# SV601286G_Schematic.net
KiCad netlist of a schematic drawn in Altium Designer
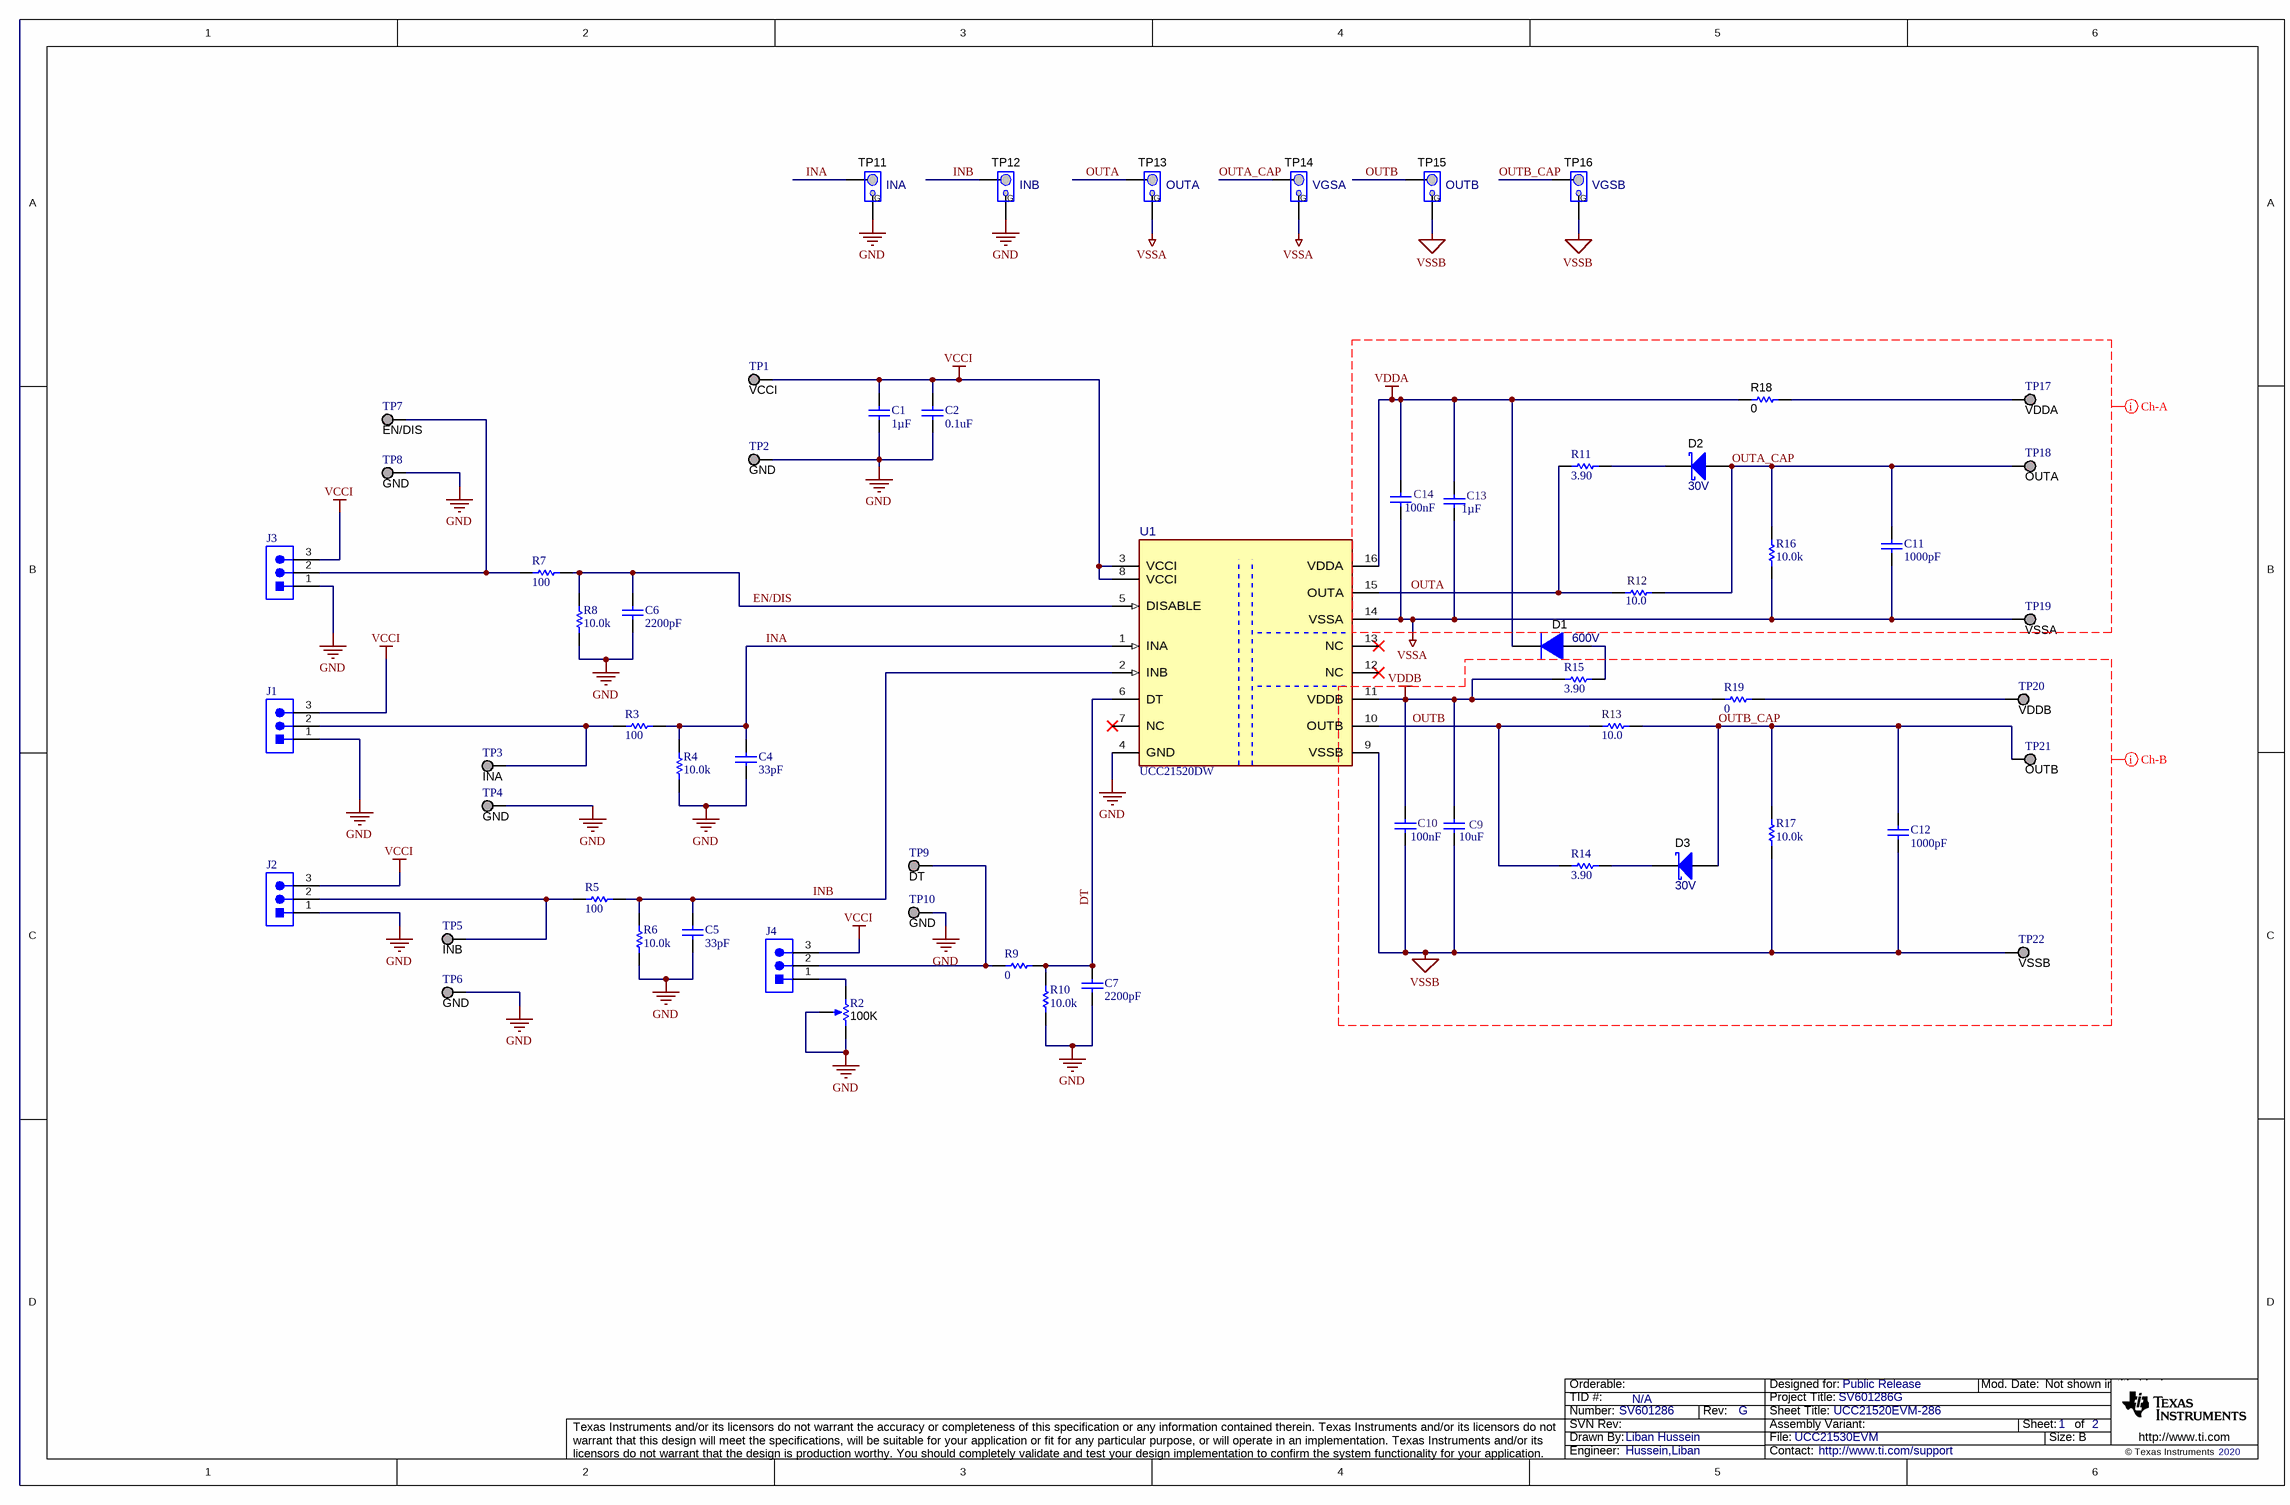
[diagram p0: SV601286G_Schematic.SchDoc]

(export (version "E")
  (design (tool "Eeschema 10.0.6"))
  (components
    (comp (ref "C1")
      (value "CL21B105KBFNFNE")
      (footprint "0805_HV1")
      (description "CAP, CERM, 1 µF, 50 V,+/- 10%, X7R, 0805")
      (fields (field (name "MANUFACTURER") "Samsung") (field (name "VALUEDISPLAYED") "1µF"))
      (libsource (lib "Altium Vault - TI") (part "Capacitor"))
    )
    (comp (ref "C2")
      (value "C1608X7R1E104K080AA")
      (footprint "0603L")
      (description "CAP, CERM, 0.1 uF, 25 V, +/- 10%, X7R, 0603")
      (fields
        (field (name "MANUFACTURER") "TDK")
        (field (name "VALUEDISPLAYED") "0.1uF")
        (field (name "PUBLISHER") "Texas Instruments")
      )
      (libsource (lib "Altium Vault - TI") (part "Capacitor"))
    )
    (comp (ref "C4")
      (value "GRM1885C1H330JA01D")
      (footprint "0603L")
      (description "CAP, CERM, 33 pF, 50 V, +/- 5%, C0G/NP0, 0603")
      (fields
        (field (name "MANUFACTURER") "MuRata")
        (field (name "VALUEDISPLAYED") "33pF")
        (field (name "PUBLISHER") "Texas Instruments")
      )
      (libsource (lib "Altium Vault - TI") (part "Capacitor"))
    )
    (comp (ref "C5")
      (value "GRM1885C1H330JA01D")
      (footprint "0603L")
      (description "CAP, CERM, 33 pF, 50 V, +/- 5%, C0G/NP0, 0603")
      (fields
        (field (name "MANUFACTURER") "MuRata")
        (field (name "VALUEDISPLAYED") "33pF")
        (field (name "PUBLISHER") "Texas Instruments")
      )
      (libsource (lib "Altium Vault - TI") (part "Capacitor"))
    )
    (comp (ref "C6")
      (value "C0603C222K5RACTU")
      (footprint "0603L")
      (description "CAP, CERM, 2200 pF, 50 V, +/- 10%, X7R, 0603")
      (fields
        (field (name "MANUFACTURER") "Kemet")
        (field (name "VALUEDISPLAYED") "2200pF")
        (field (name "PUBLISHER") "Texas Instruments")
      )
      (libsource (lib "Altium Vault - TI") (part "Capacitor"))
    )
    (comp (ref "C7")
      (value "C0603C222K5RACTU")
      (footprint "0603L")
      (description "CAP, CERM, 2200 pF, 50 V, +/- 10%, X7R, 0603")
      (fields
        (field (name "MANUFACTURER") "Kemet")
        (field (name "VALUEDISPLAYED") "2200pF")
        (field (name "PUBLISHER") "Texas Instruments")
      )
      (libsource (lib "Altium Vault - TI") (part "Capacitor"))
    )
    (comp (ref "C9")
      (value "CL31B106KBHNNNE")
      (footprint "1206_180")
      (description "CAP, CERM, 10 uF, 50 V, +/- 10%, X7R, 1206")
      (fields
        (field (name "MANUFACTURER") "Samsung")
        (field (name "VALUEDISPLAYED") "10uF")
        (field (name "PUBLISHER") "Texas Instruments")
      )
      (libsource (lib "Altium Vault - TI") (part "Capacitor"))
    )
    (comp (ref "C10")
      (value "C0805C104J5RACTU")
      (footprint "0805_HV")
      (description "CAP, CERM, 0.1 uF, 50 V, +/- 5%, X7R, 0805")
      (fields
        (field (name "MANUFACTURER") "Kemet")
        (field (name "CAP_F") "100nF")
        (field (name "PUBLISHER") "Texas Instruments")
      )
      (libsource (lib "Altium Vault - TI") (part "Capacitor"))
    )
    (comp (ref "C11")
      (value "GRM3195C1H102JA01D")
      (footprint "1206L")
      (description "CAP, CERM, 1000 pF, 50 V, +/- 5%, C0G/NP0, 1206")
      (fields
        (field (name "MANUFACTURER") "MuRata")
        (field (name "VALUEDISPLAYED") "1000pF")
        (field (name "PUBLISHER") "Texas Instruments")
      )
      (libsource (lib "Altium Vault - TI") (part "Capacitor"))
    )
    (comp (ref "C12")
      (value "GRM3195C1H102JA01D")
      (footprint "1206L")
      (description "CAP, CERM, 1000 pF, 50 V, +/- 5%, C0G/NP0, 1206")
      (fields
        (field (name "MANUFACTURER") "MuRata")
        (field (name "VALUEDISPLAYED") "1000pF")
        (field (name "PUBLISHER") "Texas Instruments")
      )
      (libsource (lib "Altium Vault - TI") (part "Capacitor"))
    )
    (comp (ref "C13")
      (value "CL21B105KBFNFNE")
      (footprint "0805_HV")
      (description "CAP, CERM, 1 µF, 50 V,+/- 10%, X7R, 0805")
      (fields (field (name "MANUFACTURER") "Samsung") (field (name "VALUEDISPLAYED") "1µF"))
      (libsource (lib "Altium Vault - TI") (part "CMP-0080611-1"))
    )
    (comp (ref "C14")
      (value "C0805C104J5RACTU")
      (footprint "0805_HV")
      (description "CAP, CERM, 0.1 uF, 50 V, +/- 5%, X7R, 0805")
      (fields
        (field (name "MANUFACTURER") "Kemet")
        (field (name "CAP_F") "100nF")
        (field (name "PUBLISHER") "Texas Instruments")
      )
      (libsource (lib "Altium Vault - TI") (part "Capacitor"))
    )
    (comp (ref "D1")
      (value "600V")
      (footprint "SMA")
      (description "Diode, Ultrafast, 600 V, 1 A, SMA")
      (fields (field (name "PARTNUMBER") "STTH1R06A") (field (name "MANUFACTURER") "STMicroelectronics"))
      (libsource (lib "Altium Vault - TI") (part "DIODE"))
    )
    (comp (ref "D2")
      (value "30V")
      (footprint "MicroSMP")
      (description "Diode, Schottky, 30 V, 1 A, AEC-Q101, MicroSMP")
      (fields
        (field (name "MANUFACTURER") "Vishay-Semiconductor")
        (field (name "PARTNUMBER") "MSS1P3L-M3/89A")
      )
      (libsource (lib "Altium Vault - TI") (part "DIODE_SCHOTTKY"))
    )
    (comp (ref "D3")
      (value "30V")
      (footprint "MicroSMP")
      (description "Diode, Schottky, 30 V, 1 A, AEC-Q101, MicroSMP")
      (fields
        (field (name "MANUFACTURER") "Vishay-Semiconductor")
        (field (name "PARTNUMBER") "MSS1P3L-M3/89A")
      )
      (libsource (lib "Altium Vault - TI") (part "DIODE_SCHOTTKY"))
    )
    (comp (ref "J1")
      (value "TSW-103-07-T-S")
      (footprint "Samtec_TSW-103-07-T-S")
      (description "Header, 2.54 mm, 3x1, Tin, TH")
      (fields (field (name "MANUFACTURER") "Samtec"))
      (libsource (lib "Altium Vault - TI") (part "Header_3x1"))
    )
    (comp (ref "J2")
      (value "TSW-103-07-T-S")
      (footprint "Samtec_TSW-103-07-T-S")
      (description "Header, 2.54 mm, 3x1, Tin, TH")
      (fields (field (name "MANUFACTURER") "Samtec"))
      (libsource (lib "Altium Vault - TI") (part "Header_3x1"))
    )
    (comp (ref "J3")
      (value "TSW-103-07-T-S")
      (footprint "Samtec_TSW-103-07-T-S")
      (description "Header, 2.54 mm, 3x1, Tin, TH")
      (fields (field (name "MANUFACTURER") "Samtec"))
      (libsource (lib "Altium Vault - TI") (part "Header_3x1"))
    )
    (comp (ref "J4")
      (value "TSW-103-07-T-S")
      (footprint "Samtec_TSW-103-07-T-S")
      (description "Header, 2.54 mm, 3x1, Tin, TH")
      (fields (field (name "MANUFACTURER") "Samtec"))
      (libsource (lib "Altium Vault - TI") (part "Header_3x1"))
    )
    (comp (ref "R2")
      (value "100K")
      (footprint "TRIM_3224X")
      (description "Trimmer, 100 K, 0.25 W, SMD")
      (fields
        (field (name "PARTNUMBER") "3224X-1-104E")
        (field (name "MANUFACTURER") "Bourns")
        (field (name "PUBLISHER") "Texas Instruments")
      )
      (libsource (lib "Altium Vault - TI") (part "Potentiometer"))
    )
    (comp (ref "R3")
      (value "CRCW0603100RFKEA")
      (footprint "0603L")
      (description "RES, 100, 1%, 0.1 W, AEC-Q200 Grade 0, 0603")
      (fields (field (name "MANUFACTURER") "Vishay-Dale") (field (name "VALUEDISPLAYED") "100"))
      (libsource (lib "Altium Vault - TI") (part "Resistor"))
    )
    (comp (ref "R4")
      (value "ERJ-3EKF1002V")
      (footprint "0603L")
      (description "RES, 10.0 k, 1%, 0.1 W, 0603")
      (fields
        (field (name "MANUFACTURER") "Panasonic")
        (field (name "VALUEDISPLAYED") "10.0k")
        (field (name "PUBLISHER") "Texas Instruments")
      )
      (libsource (lib "Altium Vault - TI") (part "CMP-0022684-3"))
    )
    (comp (ref "R5")
      (value "CRCW0603100RFKEA")
      (footprint "0603L")
      (description "RES, 100, 1%, 0.1 W, AEC-Q200 Grade 0, 0603")
      (fields (field (name "MANUFACTURER") "Vishay-Dale") (field (name "VALUEDISPLAYED") "100"))
      (libsource (lib "Altium Vault - TI") (part "Resistor"))
    )
    (comp (ref "R6")
      (value "ERJ-3EKF1002V")
      (footprint "0603L")
      (description "RES, 10.0 k, 1%, 0.1 W, 0603")
      (fields
        (field (name "MANUFACTURER") "Panasonic")
        (field (name "VALUEDISPLAYED") "10.0k")
        (field (name "PUBLISHER") "Texas Instruments")
      )
      (libsource (lib "Altium Vault - TI") (part "CMP-0022684-3"))
    )
    (comp (ref "R7")
      (value "CRCW0603100RFKEA")
      (footprint "0603_HV")
      (description "RES, 100, 1%, 0.1 W, AEC-Q200 Grade 0, 0603")
      (fields (field (name "MANUFACTURER") "Vishay-Dale") (field (name "VALUEDISPLAYED") "100"))
      (libsource (lib "Altium Vault - TI") (part "Resistor"))
    )
    (comp (ref "R8")
      (value "ERJ-3EKF1002V")
      (footprint "0603L")
      (description "RES, 10.0 k, 1%, 0.1 W, 0603")
      (fields
        (field (name "MANUFACTURER") "Panasonic")
        (field (name "VALUEDISPLAYED") "10.0k")
        (field (name "PUBLISHER") "Texas Instruments")
      )
      (libsource (lib "Altium Vault - TI") (part "Resistor"))
    )
    (comp (ref "R9")
      (value "RCS06030000Z0EA")
      (footprint "0603L")
      (description "RES, 0, 0%, 0.25 W, AEC-Q200 Grade 0, 0603")
      (fields (field (name "MANUFACTURER") "Vishay-Dale") (field (name "VALUEDISPLAYED") "0"))
      (libsource (lib "Altium Vault - TI") (part "CMP-0081973-1"))
    )
    (comp (ref "R10")
      (value "ERJ-3EKF1002V")
      (footprint "0603L")
      (description "RES, 10.0 k, 1%, 0.1 W, 0603")
      (fields
        (field (name "MANUFACTURER") "Panasonic")
        (field (name "VALUEDISPLAYED") "10.0k")
        (field (name "PUBLISHER") "Texas Instruments")
      )
      (libsource (lib "Altium Vault - TI") (part "CMP-0022684-3"))
    )
    (comp (ref "R11")
      (value "RC0805FR-073R9L")
      (footprint "0805_HV1")
      (description "RES, 3.90, 1%, 0.125 W, 0805")
      (fields
        (field (name "MANUFACTURER") "Yageo America")
        (field (name "VALUEDISPLAYED") "3.90")
        (field (name "PUBLISHER") "Texas Instruments")
      )
      (libsource (lib "Altium Vault - TI") (part "CMP-0021926-2"))
    )
    (comp (ref "R12")
      (value "ERJ-P06F10R0V")
      (footprint "0805_HV1")
      (description "RES, 10.0, 1%, 0.5 W, AEC-Q200 Grade 0, 0805")
      (fields
        (field (name "MANUFACTURER") "Panasonic")
        (field (name "VALUEDISPLAYED") "10.0")
        (field (name "PUBLISHER") "Texas Instruments")
      )
      (libsource (lib "Altium Vault - TI") (part "Resistor"))
    )
    (comp (ref "R13")
      (value "ERJ-P06F10R0V")
      (footprint "0805_HV1")
      (description "RES, 10.0, 1%, 0.5 W, AEC-Q200 Grade 0, 0805")
      (fields
        (field (name "MANUFACTURER") "Panasonic")
        (field (name "VALUEDISPLAYED") "10.0")
        (field (name "PUBLISHER") "Texas Instruments")
      )
      (libsource (lib "Altium Vault - TI") (part "Resistor"))
    )
    (comp (ref "R14")
      (value "RC0805FR-073R9L")
      (footprint "0805_HV1")
      (description "RES, 3.90, 1%, 0.125 W, 0805")
      (fields
        (field (name "MANUFACTURER") "Yageo America")
        (field (name "VALUEDISPLAYED") "3.90")
        (field (name "PUBLISHER") "Texas Instruments")
      )
      (libsource (lib "Altium Vault - TI") (part "CMP-0021926-2"))
    )
    (comp (ref "R15")
      (value "RC0805FR-073R9L")
      (footprint "0805_HV")
      (description "RES, 3.90, 1%, 0.125 W, 0805")
      (fields
        (field (name "MANUFACTURER") "Yageo America")
        (field (name "VALUEDISPLAYED") "3.90")
        (field (name "PUBLISHER") "Texas Instruments")
      )
      (libsource (lib "Altium Vault - TI") (part "CMP-0021926-2"))
    )
    (comp (ref "R16")
      (value "ERJ-3EKF1002V")
      (footprint "0603L")
      (description "RES, 10.0 k, 1%, 0.1 W, 0603")
      (fields
        (field (name "MANUFACTURER") "Panasonic")
        (field (name "VALUEDISPLAYED") "10.0k")
        (field (name "PUBLISHER") "Texas Instruments")
      )
      (libsource (lib "Altium Vault - TI") (part "CMP-0022684-3"))
    )
    (comp (ref "R17")
      (value "ERJ-3EKF1002V")
      (footprint "0603L")
      (description "RES, 10.0 k, 1%, 0.1 W, 0603")
      (fields
        (field (name "MANUFACTURER") "Panasonic")
        (field (name "VALUEDISPLAYED") "10.0k")
        (field (name "PUBLISHER") "Texas Instruments")
      )
      (libsource (lib "Altium Vault - TI") (part "CMP-0022684-3"))
    )
    (comp (ref "R18")
      (value "RCS06030000Z0EA")
      (footprint "0603L")
      (description "RES, 0, 0%, 0.25 W, AEC-Q200 Grade 0, 0603")
      (fields (field (name "MANUFACTURER") "Vishay-Dale") (field (name "VALUEDISPLAYED") "0"))
      (libsource (lib "Altium Vault - TI") (part "CMP-0081973-1"))
    )
    (comp (ref "R19")
      (value "RCS06030000Z0EA")
      (footprint "0603L")
      (description "RES, 0, 0%, 0.25 W, AEC-Q200 Grade 0, 0603")
      (fields (field (name "MANUFACTURER") "Vishay-Dale") (field (name "VALUEDISPLAYED") "0"))
      (libsource (lib "Altium Vault - TI") (part "CMP-0081973-1"))
    )
    (comp (ref "TP1")
      (value "VCCI")
      (footprint "Keystone_5019")
      (description "Test Point, Miniature, SMT")
      (fields
        (field (name "MANUFACTURER") "Keystone")
        (field (name "PARTNUMBER") "5019")
        (field (name "PUBLISHER") "Texas Instruments")
      )
      (libsource (lib "Altium Vault - TI") (part "Testpoint_Gray"))
    )
    (comp (ref "TP2")
      (value "GND")
      (footprint "Keystone_5019")
      (description "Test Point, Miniature, SMT")
      (fields
        (field (name "MANUFACTURER") "Keystone")
        (field (name "PARTNUMBER") "5019")
        (field (name "PUBLISHER") "Texas Instruments")
      )
      (libsource (lib "Altium Vault - TI") (part "Testpoint_Gray"))
    )
    (comp (ref "TP3")
      (value "INA")
      (footprint "Keystone_5019")
      (description "Test Point, Miniature, SMT")
      (fields
        (field (name "MANUFACTURER") "Keystone")
        (field (name "PARTNUMBER") "5019")
        (field (name "PUBLISHER") "Texas Instruments")
      )
      (libsource (lib "Altium Vault - TI") (part "Testpoint_Gray"))
    )
    (comp (ref "TP4")
      (value "GND")
      (footprint "Keystone_5019")
      (description "Test Point, Miniature, SMT")
      (fields
        (field (name "MANUFACTURER") "Keystone")
        (field (name "PARTNUMBER") "5019")
        (field (name "PUBLISHER") "Texas Instruments")
      )
      (libsource (lib "Altium Vault - TI") (part "Testpoint_Gray"))
    )
    (comp (ref "TP5")
      (value "INB")
      (footprint "Keystone_5019")
      (description "Test Point, Miniature, SMT")
      (fields
        (field (name "MANUFACTURER") "Keystone")
        (field (name "PARTNUMBER") "5019")
        (field (name "PUBLISHER") "Texas Instruments")
      )
      (libsource (lib "Altium Vault - TI") (part "Testpoint_Gray"))
    )
    (comp (ref "TP6")
      (value "GND")
      (footprint "Keystone_5019")
      (description "Test Point, Miniature, SMT")
      (fields
        (field (name "MANUFACTURER") "Keystone")
        (field (name "PARTNUMBER") "5019")
        (field (name "PUBLISHER") "Texas Instruments")
      )
      (libsource (lib "Altium Vault - TI") (part "Testpoint_Gray"))
    )
    (comp (ref "TP7")
      (value "EN/DIS")
      (footprint "Keystone_5019")
      (description "Test Point, Miniature, SMT")
      (fields
        (field (name "MANUFACTURER") "Keystone")
        (field (name "PARTNUMBER") "5019")
        (field (name "PUBLISHER") "Texas Instruments")
      )
      (libsource (lib "Altium Vault - TI") (part "Testpoint_Gray"))
    )
    (comp (ref "TP8")
      (value "GND")
      (footprint "Keystone_5019")
      (description "Test Point, Miniature, SMT")
      (fields
        (field (name "MANUFACTURER") "Keystone")
        (field (name "PARTNUMBER") "5019")
        (field (name "PUBLISHER") "Texas Instruments")
      )
      (libsource (lib "Altium Vault - TI") (part "Testpoint_Gray"))
    )
    (comp (ref "TP9")
      (value "DT")
      (footprint "Keystone_5019")
      (description "Test Point, Miniature, SMT")
      (fields
        (field (name "MANUFACTURER") "Keystone")
        (field (name "PARTNUMBER") "5019")
        (field (name "PUBLISHER") "Texas Instruments")
      )
      (libsource (lib "Altium Vault - TI") (part "Testpoint_Gray"))
    )
    (comp (ref "TP10")
      (value "GND")
      (footprint "Keystone_5019")
      (description "Test Point, Miniature, SMT")
      (fields
        (field (name "MANUFACTURER") "Keystone")
        (field (name "PARTNUMBER") "5019")
        (field (name "PUBLISHER") "Texas Instruments")
      )
      (libsource (lib "Altium Vault - TI") (part "Testpoint_Gray"))
    )
    (comp (ref "TP11")
      (value "INA")
      (footprint "TESTPOINT_PIGTAIL")
      (description "PIGTAIL")
      (fields
        (field (name "MANUFACTURER") "Texas Instruments")
        (field (name "PARTNUMBER") "TESTPOINT_PIGTAIL")
        (field (name "PUBLISHER") "Texas Instruments")
      )
      (libsource (lib "Altium Vault - TI") (part "TESTPOINT_PIGTAIL"))
    )
    (comp (ref "TP12")
      (value "INB")
      (footprint "TESTPOINT_PIGTAIL")
      (description "PIGTAIL")
      (fields
        (field (name "MANUFACTURER") "Texas Instruments")
        (field (name "PARTNUMBER") "TESTPOINT_PIGTAIL")
        (field (name "PUBLISHER") "Texas Instruments")
      )
      (libsource (lib "Altium Vault - TI") (part "TESTPOINT_PIGTAIL"))
    )
    (comp (ref "TP13")
      (value "OUTA")
      (footprint "TESTPOINT_PIGTAIL")
      (description "PIGTAIL")
      (fields
        (field (name "MANUFACTURER") "Texas Instruments")
        (field (name "PARTNUMBER") "TESTPOINT_PIGTAIL")
        (field (name "PUBLISHER") "Texas Instruments")
      )
      (libsource (lib "Altium Vault - TI") (part "TESTPOINT_PIGTAIL"))
    )
    (comp (ref "TP14")
      (value "VGSA")
      (footprint "TESTPOINT_PIGTAIL")
      (description "PIGTAIL")
      (fields
        (field (name "MANUFACTURER") "Texas Instruments")
        (field (name "PARTNUMBER") "TESTPOINT_PIGTAIL")
        (field (name "PUBLISHER") "Texas Instruments")
      )
      (libsource (lib "Altium Vault - TI") (part "TESTPOINT_PIGTAIL"))
    )
    (comp (ref "TP15")
      (value "OUTB")
      (footprint "TESTPOINT_PIGTAIL")
      (description "PIGTAIL")
      (fields
        (field (name "MANUFACTURER") "Texas Instruments")
        (field (name "PARTNUMBER") "TESTPOINT_PIGTAIL")
        (field (name "PUBLISHER") "Texas Instruments")
      )
      (libsource (lib "Altium Vault - TI") (part "TESTPOINT_PIGTAIL"))
    )
    (comp (ref "TP16")
      (value "VGSB")
      (footprint "TESTPOINT_PIGTAIL")
      (description "PIGTAIL")
      (fields
        (field (name "MANUFACTURER") "Texas Instruments")
        (field (name "PARTNUMBER") "TESTPOINT_PIGTAIL")
        (field (name "PUBLISHER") "Texas Instruments")
      )
      (libsource (lib "Altium Vault - TI") (part "TESTPOINT_PIGTAIL"))
    )
    (comp (ref "TP17")
      (value "VDDA")
      (footprint "Keystone_5019")
      (description "Test Point, Miniature, SMT")
      (fields
        (field (name "MANUFACTURER") "Keystone")
        (field (name "PARTNUMBER") "5019")
        (field (name "PUBLISHER") "Texas Instruments")
      )
      (libsource (lib "Altium Vault - TI") (part "Testpoint_Gray"))
    )
    (comp (ref "TP18")
      (value "OUTA")
      (footprint "Keystone_5019")
      (description "Test Point, Miniature, SMT")
      (fields
        (field (name "MANUFACTURER") "Keystone")
        (field (name "PARTNUMBER") "5019")
        (field (name "PUBLISHER") "Texas Instruments")
      )
      (libsource (lib "Altium Vault - TI") (part "Testpoint_Gray"))
    )
    (comp (ref "TP19")
      (value "VSSA")
      (footprint "Keystone_5019")
      (description "Test Point, Miniature, SMT")
      (fields
        (field (name "MANUFACTURER") "Keystone")
        (field (name "PARTNUMBER") "5019")
        (field (name "PUBLISHER") "Texas Instruments")
      )
      (libsource (lib "Altium Vault - TI") (part "Testpoint_Gray"))
    )
    (comp (ref "TP20")
      (value "VDDB")
      (footprint "Keystone_5019")
      (description "Test Point, Miniature, SMT")
      (fields
        (field (name "MANUFACTURER") "Keystone")
        (field (name "PARTNUMBER") "5019")
        (field (name "PUBLISHER") "Texas Instruments")
      )
      (libsource (lib "Altium Vault - TI") (part "Testpoint_Gray"))
    )
    (comp (ref "TP21")
      (value "OUTB")
      (footprint "Keystone_5019")
      (description "Test Point, Miniature, SMT")
      (fields
        (field (name "MANUFACTURER") "Keystone")
        (field (name "PARTNUMBER") "5019")
        (field (name "PUBLISHER") "Texas Instruments")
      )
      (libsource (lib "Altium Vault - TI") (part "Testpoint_Gray"))
    )
    (comp (ref "TP22")
      (value "VSSB")
      (footprint "Keystone_5019")
      (description "Test Point, Miniature, SMT")
      (fields
        (field (name "MANUFACTURER") "Keystone")
        (field (name "PARTNUMBER") "5019")
        (field (name "PUBLISHER") "Texas Instruments")
      )
      (libsource (lib "Altium Vault - TI") (part "Testpoint_Gray"))
    )
    (comp (ref "U1")
      (value "UCC21520DW")
      (footprint "DW0016B-MFG")
      (description "Driver 6A 2-OUT High Side/Low Side Half Brdg Non-Inv 16-Pin SOIC Tube")
      (fields
        (field (name "MANUFACTURER") "Texas Instruments")
        (field (name "DIGIKEY PART NUMBER") "296-44611-5-ND")
        (field (name "PARTNUMBER") "UCC21520DW")
      )
      (libsource (lib "Altium Vault - TI") (part "SYM-UCC21520DW"))
    )
  )
  (nets
    (net (code "1") (name "/DT") (class "Default")
      (node (ref "C7") (pin "1") (pinfunction "1_1") (pintype "passive"))
      (node (ref "R10") (pin "2") (pinfunction "2_2") (pintype "passive"))
      (node (ref "R9") (pin "2") (pinfunction "2_2") (pintype "passive"))
      (node (ref "U1") (pin "6") (pinfunction "DT_6") (pintype "passive"))
    )
    (net (code "2") (name "/EN{slash}DIS") (class "Default")
      (node (ref "C6") (pin "1") (pinfunction "1_1") (pintype "passive"))
      (node (ref "R7") (pin "2") (pinfunction "2_2") (pintype "passive"))
      (node (ref "R8") (pin "2") (pinfunction "2_2") (pintype "passive"))
      (node (ref "U1") (pin "5") (pinfunction "DISABLE_5") (pintype "input"))
    )
    (net (code "3") (name "/INA") (class "Default")
      (node (ref "C4") (pin "1") (pinfunction "1_1") (pintype "passive"))
      (node (ref "R3") (pin "2") (pinfunction "2_2") (pintype "passive"))
      (node (ref "R4") (pin "2") (pinfunction "2_2") (pintype "passive"))
      (node (ref "TP11") (pin "1") (pinfunction "1_1") (pintype "passive"))
      (node (ref "U1") (pin "1") (pinfunction "INA_1") (pintype "input"))
    )
    (net (code "4") (name "/INB") (class "Default")
      (node (ref "C5") (pin "1") (pinfunction "1_1") (pintype "passive"))
      (node (ref "R5") (pin "2") (pinfunction "2_2") (pintype "passive"))
      (node (ref "R6") (pin "2") (pinfunction "2_2") (pintype "passive"))
      (node (ref "TP12") (pin "1") (pinfunction "1_1") (pintype "passive"))
      (node (ref "U1") (pin "2") (pinfunction "INB_2") (pintype "input"))
    )
    (net (code "5") (name "/OUTA") (class "Default")
      (node (ref "R11") (pin "1") (pinfunction "1_1") (pintype "passive"))
      (node (ref "R12") (pin "1") (pinfunction "1_1") (pintype "passive"))
      (node (ref "TP13") (pin "1") (pinfunction "1_1") (pintype "passive"))
      (node (ref "U1") (pin "15") (pinfunction "OUTA_15") (pintype "passive"))
    )
    (net (code "6") (name "/OUTA_CAP") (class "Default")
      (node (ref "C11") (pin "1") (pinfunction "1_1") (pintype "passive"))
      (node (ref "D2") (pin "2") (pinfunction "A_2") (pintype "passive"))
      (node (ref "R12") (pin "2") (pinfunction "2_2") (pintype "passive"))
      (node (ref "R16") (pin "2") (pinfunction "2_2") (pintype "passive"))
      (node (ref "TP14") (pin "1") (pinfunction "1_1") (pintype "passive"))
      (node (ref "TP18") (pin "1") (pintype "passive"))
    )
    (net (code "7") (name "/OUTB") (class "Default")
      (node (ref "R13") (pin "1") (pinfunction "1_1") (pintype "passive"))
      (node (ref "R14") (pin "1") (pinfunction "1_1") (pintype "passive"))
      (node (ref "TP15") (pin "1") (pinfunction "1_1") (pintype "passive"))
      (node (ref "U1") (pin "10") (pinfunction "OUTB_10") (pintype "passive"))
    )
    (net (code "8") (name "/OUTB_CAP") (class "Default")
      (node (ref "C12") (pin "1") (pinfunction "1_1") (pintype "passive"))
      (node (ref "D3") (pin "2") (pinfunction "A_2") (pintype "passive"))
      (node (ref "R13") (pin "2") (pinfunction "2_2") (pintype "passive"))
      (node (ref "R17") (pin "2") (pinfunction "2_2") (pintype "passive"))
      (node (ref "TP16") (pin "1") (pinfunction "1_1") (pintype "passive"))
      (node (ref "TP21") (pin "1") (pintype "passive"))
    )
    (net (code "9") (name "GND") (class "Default")
      (node (ref "C1") (pin "2") (pinfunction "2_2") (pintype "passive"))
      (node (ref "C2") (pin "2") (pinfunction "2_2") (pintype "passive"))
      (node (ref "C4") (pin "2") (pinfunction "2_2") (pintype "passive"))
      (node (ref "C5") (pin "2") (pinfunction "2_2") (pintype "passive"))
      (node (ref "C6") (pin "2") (pinfunction "2_2") (pintype "passive"))
      (node (ref "C7") (pin "2") (pinfunction "2_2") (pintype "passive"))
      (node (ref "J1") (pin "1") (pinfunction "1_1") (pintype "passive"))
      (node (ref "J2") (pin "1") (pinfunction "1_1") (pintype "passive"))
      (node (ref "J3") (pin "1") (pinfunction "1_1") (pintype "passive"))
      (node (ref "R10") (pin "1") (pinfunction "1_1") (pintype "passive"))
      (node (ref "R2") (pin "2") (pinfunction "WIPER_2") (pintype "passive"))
      (node (ref "R2") (pin "3") (pinfunction "CW_3") (pintype "passive"))
      (node (ref "R4") (pin "1") (pinfunction "1_1") (pintype "passive"))
      (node (ref "R6") (pin "1") (pinfunction "1_1") (pintype "passive"))
      (node (ref "R8") (pin "1") (pinfunction "1_1") (pintype "passive"))
      (node (ref "TP10") (pin "1") (pintype "passive"))
      (node (ref "TP11") (pin "2") (pinfunction "2_2") (pintype "passive"))
      (node (ref "TP12") (pin "2") (pinfunction "2_2") (pintype "passive"))
      (node (ref "TP2") (pin "1") (pintype "passive"))
      (node (ref "TP4") (pin "1") (pintype "passive"))
      (node (ref "TP6") (pin "1") (pintype "passive"))
      (node (ref "TP8") (pin "1") (pintype "passive"))
      (node (ref "U1") (pin "4") (pinfunction "GND_4") (pintype "power_in"))
    )
    (net (code "10") (name "Net-(D1-A)") (class "Default")
      (node (ref "D1") (pin "2") (pinfunction "A_2") (pintype "passive"))
      (node (ref "R15") (pin "2") (pinfunction "2_2") (pintype "passive"))
    )
    (net (code "11") (name "Net-(D2-K)") (class "Default")
      (node (ref "D2") (pin "1") (pinfunction "K_1") (pintype "passive"))
      (node (ref "R11") (pin "2") (pinfunction "2_2") (pintype "passive"))
    )
    (net (code "12") (name "Net-(D3-K)") (class "Default")
      (node (ref "D3") (pin "1") (pinfunction "K_1") (pintype "passive"))
      (node (ref "R14") (pin "2") (pinfunction "2_2") (pintype "passive"))
    )
    (net (code "13") (name "Net-(J1-Pad2)") (class "Default")
      (node (ref "J1") (pin "2") (pinfunction "2_2") (pintype "passive"))
      (node (ref "R3") (pin "1") (pinfunction "1_1") (pintype "passive"))
      (node (ref "TP3") (pin "1") (pintype "passive"))
    )
    (net (code "14") (name "Net-(J2-Pad2)") (class "Default")
      (node (ref "J2") (pin "2") (pinfunction "2_2") (pintype "passive"))
      (node (ref "R5") (pin "1") (pinfunction "1_1") (pintype "passive"))
      (node (ref "TP5") (pin "1") (pintype "passive"))
    )
    (net (code "15") (name "Net-(J3-Pad2)") (class "Default")
      (node (ref "J3") (pin "2") (pinfunction "2_2") (pintype "passive"))
      (node (ref "R7") (pin "1") (pinfunction "1_1") (pintype "passive"))
      (node (ref "TP7") (pin "1") (pintype "passive"))
    )
    (net (code "16") (name "Net-(J4-Pad2)") (class "Default")
      (node (ref "J4") (pin "2") (pinfunction "2_2") (pintype "passive"))
      (node (ref "R9") (pin "1") (pinfunction "1_1") (pintype "passive"))
      (node (ref "TP9") (pin "1") (pintype "passive"))
    )
    (net (code "17") (name "Net-(R2-CCW)") (class "Default")
      (node (ref "J4") (pin "1") (pinfunction "1_1") (pintype "passive"))
      (node (ref "R2") (pin "1") (pinfunction "CCW_1") (pintype "passive"))
    )
    (net (code "18") (name "Net-(R18-Pad2)") (class "Default")
      (node (ref "R18") (pin "2") (pinfunction "2_2") (pintype "passive"))
      (node (ref "TP17") (pin "1") (pintype "passive"))
    )
    (net (code "19") (name "Net-(R19-Pad2)") (class "Default")
      (node (ref "R19") (pin "2") (pinfunction "2_2") (pintype "passive"))
      (node (ref "TP20") (pin "1") (pintype "passive"))
    )
    (net (code "20") (name "VCCI") (class "Default")
      (node (ref "C1") (pin "1") (pinfunction "1_1") (pintype "passive"))
      (node (ref "C2") (pin "1") (pinfunction "1_1") (pintype "passive"))
      (node (ref "J1") (pin "3") (pinfunction "3_3") (pintype "passive"))
      (node (ref "J2") (pin "3") (pinfunction "3_3") (pintype "passive"))
      (node (ref "J3") (pin "3") (pinfunction "3_3") (pintype "passive"))
      (node (ref "J4") (pin "3") (pinfunction "3_3") (pintype "passive"))
      (node (ref "TP1") (pin "1") (pintype "passive"))
      (node (ref "U1") (pin "3") (pinfunction "VCCI_3") (pintype "power_in"))
      (node (ref "U1") (pin "8") (pinfunction "VCCI_8") (pintype "power_in"))
    )
    (net (code "21") (name "VDDA") (class "Default")
      (node (ref "C13") (pin "1") (pinfunction "1_1") (pintype "passive"))
      (node (ref "C14") (pin "1") (pinfunction "1_1") (pintype "passive"))
      (node (ref "D1") (pin "1") (pinfunction "K_1") (pintype "passive"))
      (node (ref "R18") (pin "1") (pinfunction "1_1") (pintype "passive"))
      (node (ref "U1") (pin "16") (pinfunction "VDDA_16") (pintype "power_in"))
    )
    (net (code "22") (name "VDDB") (class "Default")
      (node (ref "C10") (pin "2") (pinfunction "2_2") (pintype "passive"))
      (node (ref "C9") (pin "1") (pinfunction "1_1") (pintype "passive"))
      (node (ref "R15") (pin "1") (pinfunction "1_1") (pintype "passive"))
      (node (ref "R19") (pin "1") (pinfunction "1_1") (pintype "passive"))
      (node (ref "U1") (pin "11") (pinfunction "VDDB_11") (pintype "power_in"))
    )
    (net (code "23") (name "VSSA") (class "Default")
      (node (ref "C11") (pin "2") (pinfunction "2_2") (pintype "passive"))
      (node (ref "C13") (pin "2") (pinfunction "2_2") (pintype "passive"))
      (node (ref "C14") (pin "2") (pinfunction "2_2") (pintype "passive"))
      (node (ref "R16") (pin "1") (pinfunction "1_1") (pintype "passive"))
      (node (ref "TP13") (pin "2") (pinfunction "2_2") (pintype "passive"))
      (node (ref "TP14") (pin "2") (pinfunction "2_2") (pintype "passive"))
      (node (ref "TP19") (pin "1") (pintype "passive"))
      (node (ref "U1") (pin "14") (pinfunction "VSSA_14") (pintype "power_in"))
    )
    (net (code "24") (name "VSSB") (class "Default")
      (node (ref "C10") (pin "1") (pinfunction "1_1") (pintype "passive"))
      (node (ref "C12") (pin "2") (pinfunction "2_2") (pintype "passive"))
      (node (ref "C9") (pin "2") (pinfunction "2_2") (pintype "passive"))
      (node (ref "R17") (pin "1") (pinfunction "1_1") (pintype "passive"))
      (node (ref "TP15") (pin "2") (pinfunction "2_2") (pintype "passive"))
      (node (ref "TP16") (pin "2") (pinfunction "2_2") (pintype "passive"))
      (node (ref "TP22") (pin "1") (pintype "passive"))
      (node (ref "U1") (pin "9") (pinfunction "VSSB_9") (pintype "power_in"))
    )
    (net (code "25") (name "unconnected-(U1-NC-Pad7)") (class "Default")
      (node (ref "U1") (pin "7") (pinfunction "NC_7") (pintype "passive+no_connect"))
    )
    (net (code "26") (name "unconnected-(U1-NC-Pad12)") (class "Default")
      (node (ref "U1") (pin "12") (pinfunction "NC_12") (pintype "passive+no_connect"))
    )
    (net (code "27") (name "unconnected-(U1-NC-Pad13)") (class "Default")
      (node (ref "U1") (pin "13") (pinfunction "NC_13") (pintype "passive+no_connect"))
    )
  )
)
